# Sheet2.net
KiCad netlist of a schematic drawn in Altium Designer
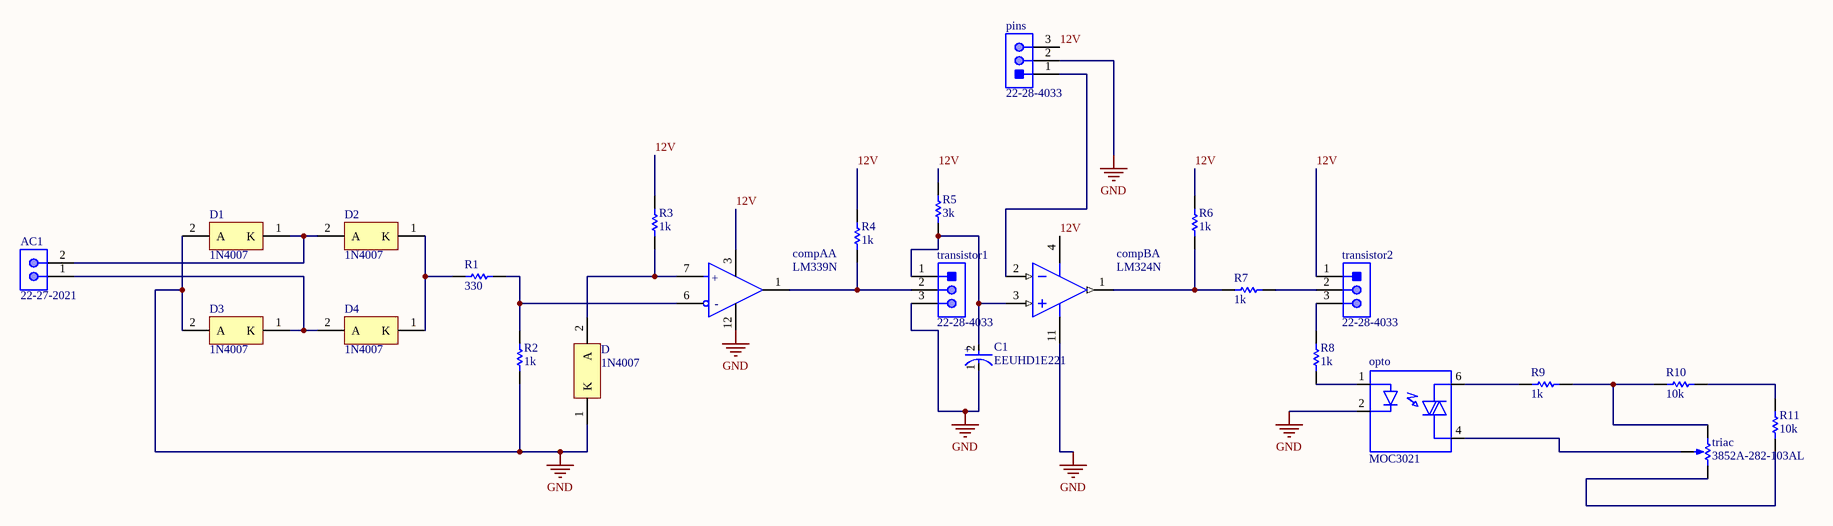
[diagram p0: Sheet2.SchDoc]

(export (version "E")
  (design (tool "Eeschema 10.0.6"))
  (components
    (comp (ref "AC1")
      (value "22-27-2021")
      (footprint "MOLX-22-27-2021_V")
      (fields (field (name "MANUFACTURER") "Molex") (field (name "PARTNUMBER") "0022272021"))
      (libsource (lib "Altium Content Vault") (part "CN-1P-M-R2"))
    )
    (comp (ref "C1")
      (value "EEUHD1E221")
      (footprint "FP-RAD-TH-D_8_0_5-L_11_5-MFG")
      (description "Aluminum Electrolytic Capacitors (Radial Lead Type) AEC-Q200 Qualified 220uF ±20% 25V")
      (fields (field (name "VOLTAGE") "25V") (field (name "TOLERANCE") "20%"))
      (libsource (lib "Altium Content Vault") (part "a00bbbee19879c290e62620ae7e47b1"))
    )
    (comp (ref "compA")
      (value "LM339N")
      (footprint "FP-N0014A-MFG")
      (description "IC QUAD DIFF COMPARATOR 14-DIP")
      (libsource (lib "Altium Content Vault") (part "8b3fbf4f291bf98688575f76bf8ab1e"))
    )
    (comp (ref "compB")
      (value "LM324N")
      (footprint "N0014A")
      (description "Low Power Quad Operational Amplifier, 14-pin MDIP")
      (fields (field (name "MANUFACTURER") "Texas Instruments"))
      (libsource (lib "Altium Content Vault") (part "AMP-OPA-LM124-14"))
    )
    (comp (ref "D")
      (value "1N4007")
      (footprint "ONSC-AXIAL_LEAD-2-59-10_P")
      (description "Standard Recovery Rectifier, 2-Pin Axial_Lead, Pb-Free, Bulk Bag")
      (fields (field (name "MANUFACTURER") "On Semiconductor"))
      (libsource (lib "") (part "ONSC-D-K1A2-2_A_1"))
    )
    (comp (ref "D1")
      (value "1N4007")
      (footprint "ONSC-AXIAL_LEAD-2-59-10_P")
      (description "Standard Recovery Rectifier, 2-Pin Axial_Lead, Pb-Free, Bulk Bag")
      (fields (field (name "MANUFACTURER") "On Semiconductor"))
      (libsource (lib "Altium Content Vault") (part "ONSC-D-K1A2-2_A"))
    )
    (comp (ref "D2")
      (value "1N4007")
      (footprint "ONSC-AXIAL_LEAD-2-59-10_P")
      (description "Standard Recovery Rectifier, 2-Pin Axial_Lead, Pb-Free, Bulk Bag")
      (fields (field (name "MANUFACTURER") "On Semiconductor"))
      (libsource (lib "Altium Content Vault") (part "ONSC-D-K1A2-2_A"))
    )
    (comp (ref "D3")
      (value "1N4007")
      (footprint "ONSC-AXIAL_LEAD-2-59-10_P")
      (description "Standard Recovery Rectifier, 2-Pin Axial_Lead, Pb-Free, Bulk Bag")
      (fields (field (name "MANUFACTURER") "On Semiconductor"))
      (libsource (lib "Altium Content Vault") (part "ONSC-D-K1A2-2_A"))
    )
    (comp (ref "D4")
      (value "1N4007")
      (footprint "ONSC-AXIAL_LEAD-2-59-10_P")
      (description "Standard Recovery Rectifier, 2-Pin Axial_Lead, Pb-Free, Bulk Bag")
      (fields (field (name "MANUFACTURER") "On Semiconductor"))
      (libsource (lib "Altium Content Vault") (part "ONSC-D-K1A2-2_A"))
    )
    (comp (ref "opto")
      (value "MOC3021")
      (footprint "DIP762W45P254L889H508Q6")
      (description "Optoisolator Triac Output 5000Vrms 1 Channel 6-DIP")
      (fields (field (name "MF") "Lite-On"))
      (libsource (lib "MOC3021") (part "MOC3021"))
    )
    (comp (ref "pins")
      (value "22-28-4033")
      (footprint "MOLX-22-28-4033_V")
      (description "Male Header, Pitch 2.54 mm, 1 x 3 Position, Height 8.38 mm, Tail Length 3.18 mm, RoHS, Bulk")
      (fields (field (name "MANUFACTURER") "Molex"))
      (libsource (lib "") (part "CN-1P-M-R3_1"))
    )
    (comp (ref "R1")
      (value "330")
      (footprint "RESA60-630X240")
      (description "Axial Resistor, 1 KOhm, +/- 1%, 250 mW, -55 to 155 degC, 2-Pin THD, RoHS, Bulk")
      (fields (field (name "TOLERANCE") "1%"))
      (libsource (lib "Altium Content Vault") (part "RES-2"))
    )
    (comp (ref "R2")
      (value "1k")
      (footprint "RESA60-630X240")
      (description "Axial Resistor, 1 KOhm, +/- 1%, 250 mW, -55 to 155 degC, 2-Pin THD, RoHS, Bulk")
      (fields (field (name "TOLERANCE") "1%"))
      (libsource (lib "Altium Content Vault") (part "RES-2"))
    )
    (comp (ref "R3")
      (value "1k")
      (footprint "RESA60-630X240")
      (description "Axial Resistor, 1 KOhm, +/- 1%, 250 mW, -55 to 155 degC, 2-Pin THD, RoHS, Bulk")
      (fields (field (name "TOLERANCE") "1%"))
      (libsource (lib "Altium Content Vault") (part "RES-2"))
    )
    (comp (ref "R4")
      (value "1k")
      (footprint "RESA60-630X240")
      (description "Axial Resistor, 1 KOhm, +/- 1%, 250 mW, -55 to 155 degC, 2-Pin THD, RoHS, Bulk")
      (fields (field (name "TOLERANCE") "1%"))
      (libsource (lib "Altium Content Vault") (part "RES-2"))
    )
    (comp (ref "R5")
      (value "3k")
      (footprint "RESA60-630X240")
      (description "Axial Resistor, 1 KOhm, +/- 1%, 250 mW, -55 to 155 degC, 2-Pin THD, RoHS, Bulk")
      (fields (field (name "TOLERANCE") "1%"))
      (libsource (lib "Altium Content Vault") (part "RES-2"))
    )
    (comp (ref "R6")
      (value "1k")
      (footprint "RESA60-630X240")
      (description "Axial Resistor, 1 KOhm, +/- 1%, 250 mW, -55 to 155 degC, 2-Pin THD, RoHS, Bulk")
      (fields (field (name "TOLERANCE") "1%"))
      (libsource (lib "Altium Content Vault") (part "RES-2"))
    )
    (comp (ref "R7")
      (value "1k")
      (footprint "RESA60-630X240")
      (description "Axial Resistor, 1 KOhm, +/- 1%, 250 mW, -55 to 155 degC, 2-Pin THD, RoHS, Bulk")
      (fields (field (name "TOLERANCE") "1%"))
      (libsource (lib "Altium Content Vault") (part "RES-2"))
    )
    (comp (ref "R8")
      (value "1k")
      (footprint "RESA60-630X240")
      (description "Axial Resistor, 1 KOhm, +/- 1%, 250 mW, -55 to 155 degC, 2-Pin THD, RoHS, Bulk")
      (fields (field (name "TOLERANCE") "1%"))
      (libsource (lib "Altium Content Vault") (part "RES-2"))
    )
    (comp (ref "R9")
      (value "1k")
      (footprint "RESA60-630X240")
      (description "Axial Resistor, 1 KOhm, +/- 1%, 250 mW, -55 to 155 degC, 2-Pin THD, RoHS, Bulk")
      (fields (field (name "TOLERANCE") "1%"))
      (libsource (lib "Altium Content Vault") (part "RES-2"))
    )
    (comp (ref "R10")
      (value "10k")
      (footprint "RESA60-630X240")
      (description "Axial Resistor, 1 KOhm, +/- 1%, 250 mW, -55 to 155 degC, 2-Pin THD, RoHS, Bulk")
      (fields (field (name "TOLERANCE") "1%"))
      (libsource (lib "Altium Content Vault") (part "RES-2"))
    )
    (comp (ref "R11")
      (value "10k")
      (footprint "RESA60-630X240")
      (description "Axial Resistor, 1 KOhm, +/- 1%, 250 mW, -55 to 155 degC, 2-Pin THD, RoHS, Bulk")
      (fields (field (name "TOLERANCE") "1%"))
      (libsource (lib "Altium Content Vault") (part "RES-2"))
    )
    (comp (ref "transistor1")
      (value "22-28-4033")
      (footprint "MOLX-22-28-4033_V")
      (description "Male Header, Pitch 2.54 mm, 1 x 3 Position, Height 8.38 mm, Tail Length 3.18 mm, RoHS, Bulk")
      (fields (field (name "MANUFACTURER") "Molex"))
      (libsource (lib "Altium Content Vault") (part "CN-1P-M-R3"))
    )
    (comp (ref "transistor2")
      (value "22-28-4033")
      (footprint "MOLX-22-28-4033_V")
      (description "Male Header, Pitch 2.54 mm, 1 x 3 Position, Height 8.38 mm, Tail Length 3.18 mm, RoHS, Bulk")
      (fields (field (name "MANUFACTURER") "Molex"))
      (libsource (lib "Altium Content Vault") (part "CN-1P-M-R3"))
    )
    (comp (ref "triac")
      (value "3852A-282-103AL")
      (footprint "BOUR-3852A-282-103AL-3_V")
      (description "Diameter Panel Control, 10 KOhm, +/- 10%, 2 W, -1 to 125 degC, 3-Pin THD, RoHS, Bulk")
      (fields (field (name "TOLERANCE") "±10%") (field (name "MANUFACTURER") "Bourns"))
      (libsource (lib "Altium Content Vault") (part "RES-POT-3"))
    )
  )
  (nets
    (net (code "1") (name "/12V") (class "Default")
      (node (ref "R3") (pin "1") (pinfunction "1_1") (pintype "passive"))
      (node (ref "R4") (pin "1") (pinfunction "1_1") (pintype "passive"))
      (node (ref "R5") (pin "1") (pinfunction "1_1") (pintype "passive"))
      (node (ref "R6") (pin "1") (pinfunction "1_1") (pintype "passive"))
      (node (ref "compA") (pin "3") (pinfunction "VCC_3") (pintype "power_in"))
      (node (ref "compB") (pin "4") (pinfunction "V+_4") (pintype "power_in"))
      (node (ref "pins") (pin "3") (pinfunction "3_3") (pintype "passive"))
      (node (ref "transistor2") (pin "1") (pinfunction "1_1") (pintype "passive"))
    )
    (net (code "2") (name "GND") (class "Default")
      (node (ref "C1") (pin "1") (pinfunction "C_1") (pintype "passive"))
      (node (ref "D") (pin "1") (pinfunction "K_1") (pintype "passive"))
      (node (ref "D1") (pin "2") (pinfunction "A_2") (pintype "passive"))
      (node (ref "D3") (pin "2") (pinfunction "A_2") (pintype "passive"))
      (node (ref "R2") (pin "2") (pinfunction "2_2") (pintype "passive"))
      (node (ref "compA") (pin "12") (pinfunction "GND_12") (pintype "power_in"))
      (node (ref "compB") (pin "11") (pinfunction "GND_11") (pintype "power_in"))
      (node (ref "opto") (pin "2") (pinfunction "CATODE_2") (pintype "passive"))
      (node (ref "pins") (pin "2") (pinfunction "2_2") (pintype "passive"))
      (node (ref "transistor1") (pin "3") (pinfunction "3_3") (pintype "passive"))
    )
    (net (code "3") (name "Net-(C1-A)") (class "Default")
      (node (ref "C1") (pin "2") (pinfunction "A_2") (pintype "passive"))
      (node (ref "R5") (pin "2") (pinfunction "2_2") (pintype "passive"))
      (node (ref "compB") (pin "3") (pinfunction "IN1+_3") (pintype "input"))
      (node (ref "transistor1") (pin "1") (pinfunction "1_1") (pintype "passive"))
    )
    (net (code "4") (name "Net-(D-A)") (class "Default")
      (node (ref "D") (pin "2") (pinfunction "A_2") (pintype "passive"))
      (node (ref "R3") (pin "2") (pinfunction "2_2") (pintype "passive"))
      (node (ref "compA") (pin "7") (pinfunction "1IN+_7") (pintype "tri_state"))
    )
    (net (code "5") (name "Net-(D1-K)") (class "Default")
      (node (ref "AC1") (pin "2") (pinfunction "2_2") (pintype "passive"))
      (node (ref "D1") (pin "1") (pinfunction "K_1") (pintype "passive"))
      (node (ref "D2") (pin "2") (pinfunction "A_2") (pintype "passive"))
    )
    (net (code "6") (name "Net-(D2-K)") (class "Default")
      (node (ref "D2") (pin "1") (pinfunction "K_1") (pintype "passive"))
      (node (ref "D4") (pin "1") (pinfunction "K_1") (pintype "passive"))
      (node (ref "R1") (pin "2") (pinfunction "2_2") (pintype "passive"))
    )
    (net (code "7") (name "Net-(D3-K)") (class "Default")
      (node (ref "AC1") (pin "1") (pinfunction "1_1") (pintype "passive"))
      (node (ref "D3") (pin "1") (pinfunction "K_1") (pintype "passive"))
      (node (ref "D4") (pin "2") (pinfunction "A_2") (pintype "passive"))
    )
    (net (code "8") (name "Net-(R7-Pad1)") (class "Default")
      (node (ref "R7") (pin "1") (pinfunction "1_1") (pintype "passive"))
      (node (ref "transistor2") (pin "2") (pinfunction "2_2") (pintype "passive"))
    )
    (net (code "9") (name "Net-(R8-Pad1)") (class "Default")
      (node (ref "R8") (pin "1") (pinfunction "1_1") (pintype "passive"))
      (node (ref "transistor2") (pin "3") (pinfunction "3_3") (pintype "passive"))
    )
    (net (code "10") (name "Net-(R10-Pad2)") (class "Default")
      (node (ref "R10") (pin "2") (pinfunction "2_2") (pintype "passive"))
      (node (ref "R11") (pin "2") (pinfunction "2_2") (pintype "passive"))
    )
    (net (code "11") (name "Net-(compAA-1IN-)") (class "Default")
      (node (ref "R1") (pin "1") (pinfunction "1_1") (pintype "passive"))
      (node (ref "R2") (pin "1") (pinfunction "1_1") (pintype "passive"))
      (node (ref "compA") (pin "6") (pinfunction "1IN-_6") (pintype "tri_state"))
    )
    (net (code "12") (name "Net-(compAA-1OUT)") (class "Default")
      (node (ref "R4") (pin "2") (pinfunction "2_2") (pintype "passive"))
      (node (ref "compA") (pin "1") (pinfunction "1OUT_1") (pintype "passive"))
      (node (ref "transistor1") (pin "2") (pinfunction "2_2") (pintype "passive"))
    )
    (net (code "13") (name "Net-(compBA-IN1-)") (class "Default")
      (node (ref "compB") (pin "2") (pinfunction "IN1-_2") (pintype "input"))
      (node (ref "pins") (pin "1") (pinfunction "1_1") (pintype "passive"))
    )
    (net (code "14") (name "Net-(compBA-OUT1)") (class "Default")
      (node (ref "R6") (pin "2") (pinfunction "2_2") (pintype "passive"))
      (node (ref "R7") (pin "2") (pinfunction "2_2") (pintype "passive"))
      (node (ref "compB") (pin "1") (pinfunction "OUT1_1") (pintype "output"))
    )
    (net (code "15") (name "Net-(opto-ANODE)") (class "Default")
      (node (ref "R8") (pin "2") (pinfunction "2_2") (pintype "passive"))
      (node (ref "opto") (pin "1") (pinfunction "ANODE_1") (pintype "passive"))
    )
    (net (code "16") (name "Net-(opto-MAIN_TERM1)") (class "Default")
      (node (ref "R9") (pin "2") (pinfunction "2_2") (pintype "passive"))
      (node (ref "opto") (pin "6") (pinfunction "MAIN_TERM1_6") (pintype "passive"))
    )
    (net (code "17") (name "Net-(opto-MAIN_TERM2)") (class "Default")
      (node (ref "opto") (pin "4") (pinfunction "MAIN_TERM2_4") (pintype "passive"))
      (node (ref "triac") (pin "2") (pinfunction "S_2") (pintype "passive"))
    )
    (net (code "18") (name "Net-(triac-CCW)") (class "Default")
      (node (ref "R10") (pin "1") (pinfunction "1_1") (pintype "passive"))
      (node (ref "R9") (pin "1") (pinfunction "1_1") (pintype "passive"))
      (node (ref "triac") (pin "1") (pinfunction "CCW_1") (pintype "passive"))
    )
    (net (code "19") (name "Net-(triac-CW)") (class "Default")
      (node (ref "R11") (pin "1") (pinfunction "1_1") (pintype "passive"))
      (node (ref "triac") (pin "3") (pinfunction "CW_3") (pintype "passive"))
    )
  )
)
